# pi.net
KiCad netlist of a schematic drawn in EAGLE
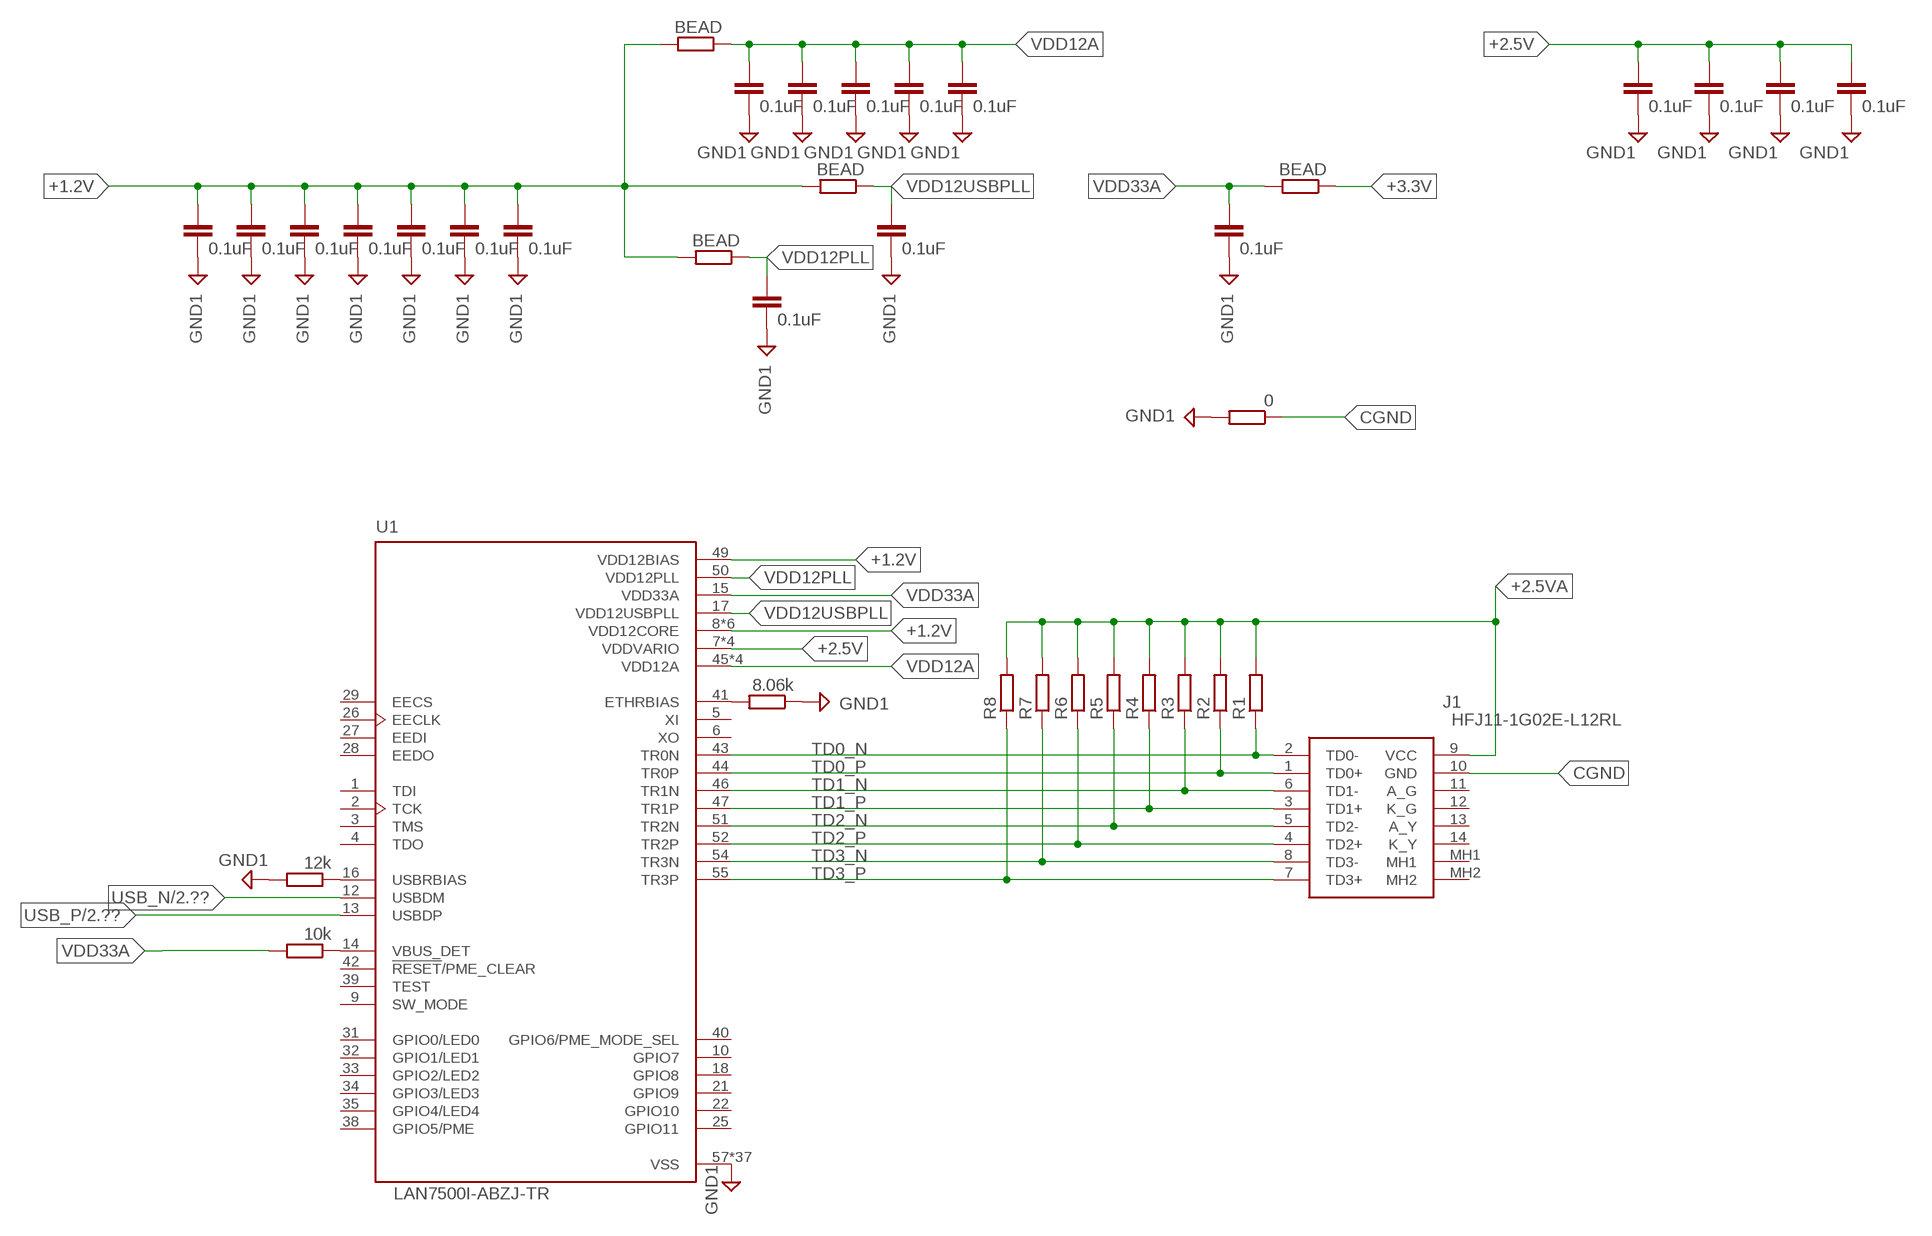
[diagram p0: schematic, sheet 1]
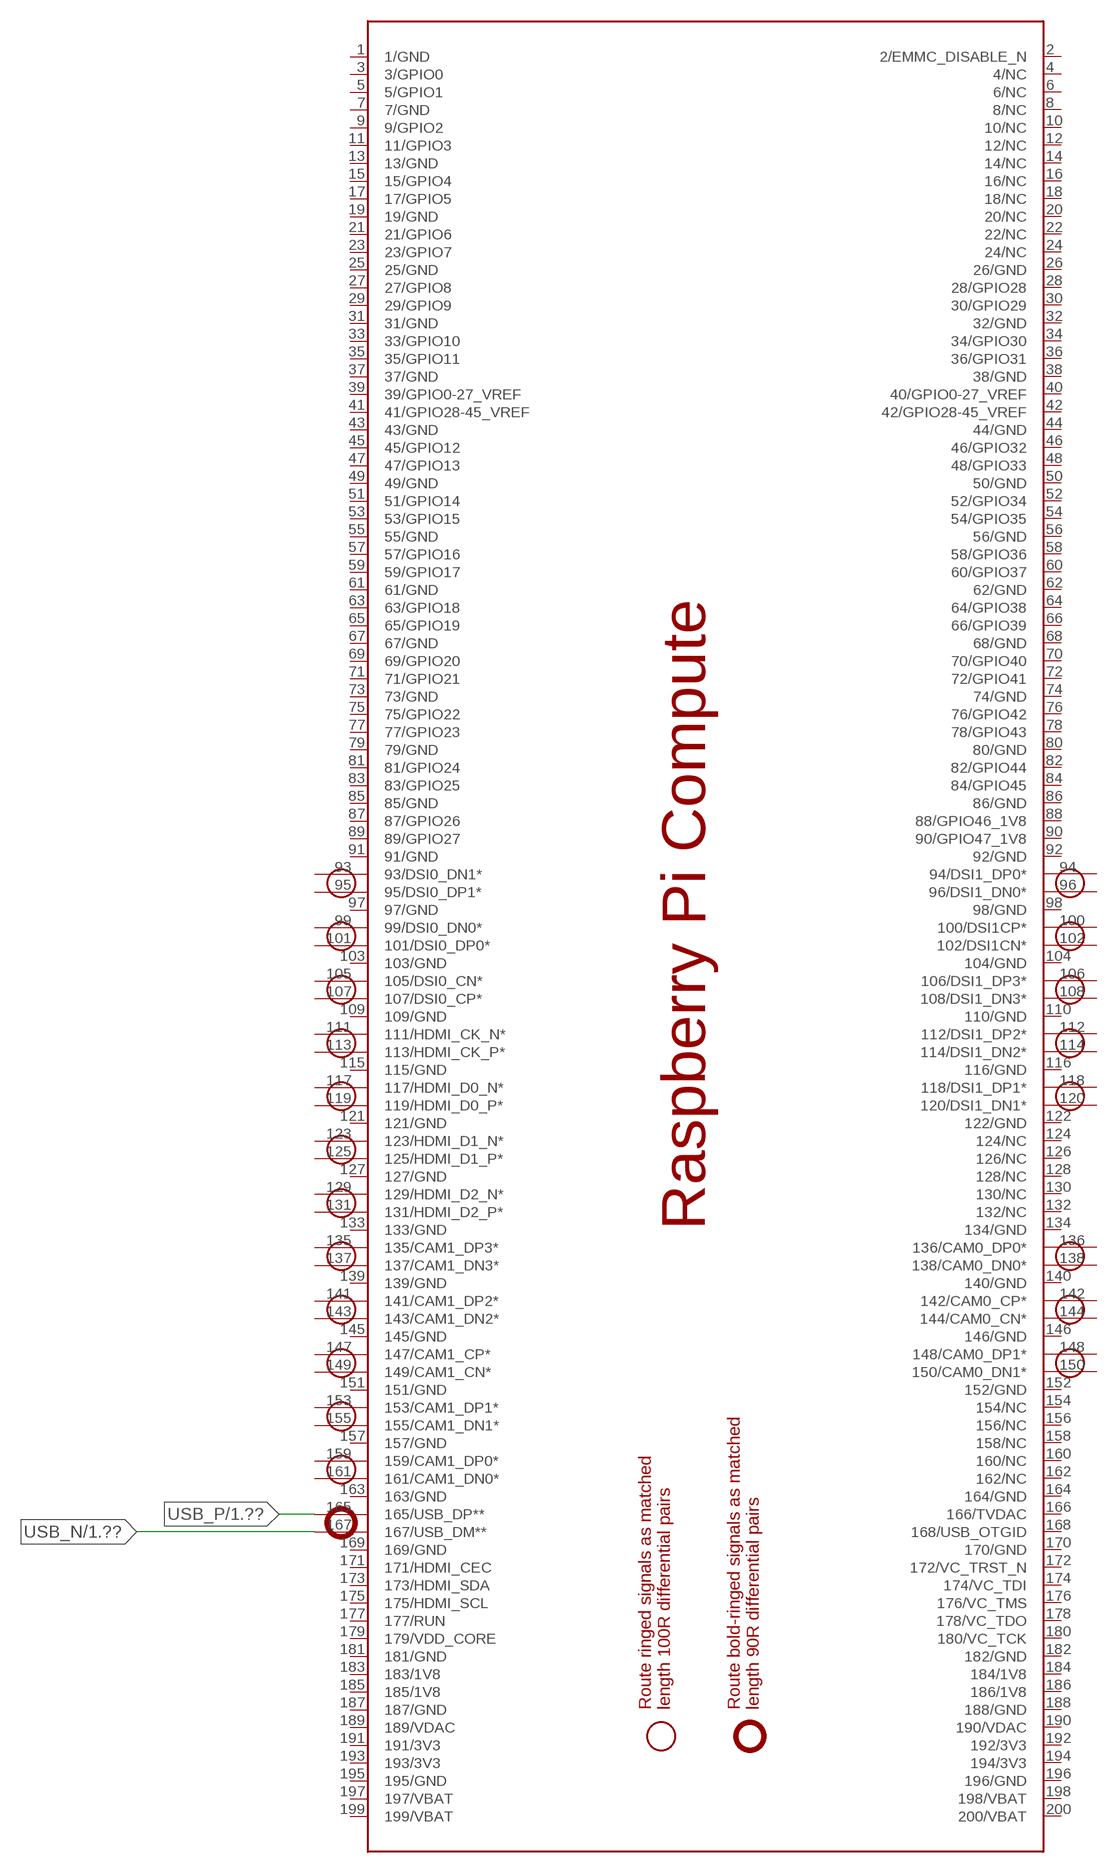
[diagram p1: schematic, sheet 2]
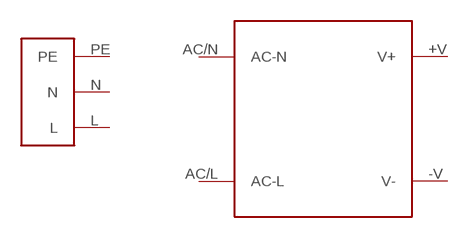
[diagram p2: schematic, sheet 3]

(export (version "E")
  (design (tool "Eeschema 10.0.6"))
  (components
    (comp (ref "U$1")
      (value "DD21")
      (footprint "eagle-import:DD21.NOCOVER")
      (libsource (lib "eagle-import") (part "DD21"))
    )
    (comp (ref "U$2")
      (value "IRM-15-5")
      (footprint "eagle-import:IRM-15")
      (libsource (lib "eagle-import") (part "IRM-15-5"))
    )
    (comp (ref "PCB1")
      (value "RPI_COMPUTE")
      (footprint "eagle-import:RPI_COMPUTE")
      (libsource (lib "eagle-import") (part "RPI_COMPUTE"))
    )
    (comp (ref "C1")
      (value "0.1uF")
      (footprint "eagle-import:C0603K")
      (libsource (lib "eagle-import") (part "C-EUC0603K"))
    )
    (comp (ref "C2")
      (value "0.1uF")
      (footprint "eagle-import:C0603K")
      (libsource (lib "eagle-import") (part "C-EUC0603K"))
    )
    (comp (ref "C3")
      (value "0.1uF")
      (footprint "eagle-import:C0603K")
      (libsource (lib "eagle-import") (part "C-EUC0603K"))
    )
    (comp (ref "C4")
      (value "0.1uF")
      (footprint "eagle-import:C0603K")
      (libsource (lib "eagle-import") (part "C-EUC0603K"))
    )
    (comp (ref "C5")
      (value "0.1uF")
      (footprint "eagle-import:C0603K")
      (libsource (lib "eagle-import") (part "C-EUC0603K"))
    )
    (comp (ref "C6")
      (value "0.1uF")
      (footprint "eagle-import:C0603K")
      (libsource (lib "eagle-import") (part "C-EUC0603K"))
    )
    (comp (ref "C7")
      (value "0.1uF")
      (footprint "eagle-import:C0603K")
      (libsource (lib "eagle-import") (part "C-EUC0603K"))
    )
    (comp (ref "C8")
      (value "0.1uF")
      (footprint "eagle-import:C0603K")
      (libsource (lib "eagle-import") (part "C-EUC0603K"))
    )
    (comp (ref "C9")
      (value "0.1uF")
      (footprint "eagle-import:C0603K")
      (libsource (lib "eagle-import") (part "C-EUC0603K"))
    )
    (comp (ref "C10")
      (value "0.1uF")
      (footprint "eagle-import:C0603K")
      (libsource (lib "eagle-import") (part "C-EUC0603K"))
    )
    (comp (ref "C11")
      (value "0.1uF")
      (footprint "eagle-import:C0603K")
      (libsource (lib "eagle-import") (part "C-EUC0603K"))
    )
    (comp (ref "C12")
      (value "0.1uF")
      (footprint "eagle-import:C0603K")
      (libsource (lib "eagle-import") (part "C-EUC0603K"))
    )
    (comp (ref "C13")
      (value "0.1uF")
      (footprint "eagle-import:C0603K")
      (libsource (lib "eagle-import") (part "C-EUC0603K"))
    )
    (comp (ref "C14")
      (value "0.1uF")
      (footprint "eagle-import:C0603K")
      (libsource (lib "eagle-import") (part "C-EUC0603K"))
    )
    (comp (ref "C15")
      (value "0.1uF")
      (footprint "eagle-import:C0603K")
      (libsource (lib "eagle-import") (part "C-EUC0603K"))
    )
    (comp (ref "C16")
      (value "0.1uF")
      (footprint "eagle-import:C0603K")
      (libsource (lib "eagle-import") (part "C-EUC0603K"))
    )
    (comp (ref "C17")
      (value "0.1uF")
      (footprint "eagle-import:C0603K")
      (libsource (lib "eagle-import") (part "C-EUC0603K"))
    )
    (comp (ref "C18")
      (value "0.1uF")
      (footprint "eagle-import:C0603K")
      (libsource (lib "eagle-import") (part "C-EUC0603K"))
    )
    (comp (ref "C19")
      (value "0.1uF")
      (footprint "eagle-import:C0603K")
      (libsource (lib "eagle-import") (part "C-EUC0603K"))
    )
    (comp (ref "J1")
      (value "HFJ11-1G02E-L12RL")
      (footprint "eagle-import:HFJ111G02EL12RL")
      (fields (field (name "MOUSER_PART_NUMBER") "493-HFJ111G02EL12RL"))
      (libsource (lib "eagle-import") (part "HFJ11-1G02E-L12RL"))
    )
    (comp (ref "R1")
      (value "R-EU_MELF0204R")
      (footprint "eagle-import:MINI_MELF-0204R")
      (libsource (lib "eagle-import") (part "R-EU_MELF0204R"))
    )
    (comp (ref "R2")
      (value "R-EU_MELF0204R")
      (footprint "eagle-import:MINI_MELF-0204R")
      (libsource (lib "eagle-import") (part "R-EU_MELF0204R"))
    )
    (comp (ref "R3")
      (value "R-EU_MELF0204R")
      (footprint "eagle-import:MINI_MELF-0204R")
      (libsource (lib "eagle-import") (part "R-EU_MELF0204R"))
    )
    (comp (ref "R4")
      (value "R-EU_MELF0204R")
      (footprint "eagle-import:MINI_MELF-0204R")
      (libsource (lib "eagle-import") (part "R-EU_MELF0204R"))
    )
    (comp (ref "R5")
      (value "R-EU_MELF0204R")
      (footprint "eagle-import:MINI_MELF-0204R")
      (libsource (lib "eagle-import") (part "R-EU_MELF0204R"))
    )
    (comp (ref "R6")
      (value "R-EU_MELF0204R")
      (footprint "eagle-import:MINI_MELF-0204R")
      (libsource (lib "eagle-import") (part "R-EU_MELF0204R"))
    )
    (comp (ref "R7")
      (value "R-EU_MELF0204R")
      (footprint "eagle-import:MINI_MELF-0204R")
      (libsource (lib "eagle-import") (part "R-EU_MELF0204R"))
    )
    (comp (ref "R8")
      (value "R-EU_MELF0204R")
      (footprint "eagle-import:MINI_MELF-0204R")
      (libsource (lib "eagle-import") (part "R-EU_MELF0204R"))
    )
    (comp (ref "R9")
      (value "8.06k")
      (footprint "eagle-import:MINI_MELF-0204R")
      (libsource (lib "eagle-import") (part "R-EU_MELF0204R"))
    )
    (comp (ref "R10")
      (value "12k")
      (footprint "eagle-import:MINI_MELF-0204R")
      (libsource (lib "eagle-import") (part "R-EU_MELF0204R"))
    )
    (comp (ref "R11")
      (value "10k")
      (footprint "eagle-import:MINI_MELF-0204R")
      (libsource (lib "eagle-import") (part "R-EU_MELF0204R"))
    )
    (comp (ref "R12")
      (value "BEAD")
      (footprint "eagle-import:MINI_MELF-0204R")
      (libsource (lib "eagle-import") (part "R-EU_MELF0204R"))
    )
    (comp (ref "R13")
      (value "BEAD")
      (footprint "eagle-import:MINI_MELF-0204R")
      (libsource (lib "eagle-import") (part "R-EU_MELF0204R"))
    )
    (comp (ref "R14")
      (value "BEAD")
      (footprint "eagle-import:MINI_MELF-0204R")
      (libsource (lib "eagle-import") (part "R-EU_MELF0204R"))
    )
    (comp (ref "R15")
      (value "0")
      (footprint "eagle-import:MINI_MELF-0204R")
      (libsource (lib "eagle-import") (part "R-EU_MELF0204R"))
    )
    (comp (ref "R16")
      (value "BEAD")
      (footprint "eagle-import:MINI_MELF-0204R")
      (libsource (lib "eagle-import") (part "R-EU_MELF0204R"))
    )
    (comp (ref "U1")
      (value "LAN7500I-ABZJ-TR")
      (footprint "eagle-import:QFN50P800X800X100-57N")
      (fields (field (name "MF") "Microchip"))
      (libsource (lib "eagle-import") (part "LAN7500I-ABZJ-TR"))
    )
  )
  (nets
    (net (code "1") (name "+1.2V") (class "Default")
      (node (ref "C19") (pin "1") (pinfunction "1_1") (pintype "passive"))
      (node (ref "C4") (pin "1") (pinfunction "1_1") (pintype "passive"))
      (node (ref "C5") (pin "1") (pinfunction "1_1") (pintype "passive"))
      (node (ref "C6") (pin "1") (pinfunction "1_1") (pintype "passive"))
      (node (ref "C7") (pin "1") (pinfunction "1_1") (pintype "passive"))
      (node (ref "C8") (pin "1") (pinfunction "1_1") (pintype "passive"))
      (node (ref "C9") (pin "1") (pinfunction "1_1") (pintype "passive"))
      (node (ref "R12") (pin "2") (pinfunction "2_2") (pintype "passive"))
      (node (ref "R13") (pin "2") (pinfunction "2_2") (pintype "passive"))
      (node (ref "R16") (pin "2") (pinfunction "2_2") (pintype "passive"))
      (node (ref "U1") (pin "11") (pinfunction "VDD12CORE_11") (pintype "power_in"))
      (node (ref "U1") (pin "20") (pinfunction "VDD12CORE_20") (pintype "power_in"))
      (node (ref "U1") (pin "23") (pinfunction "VDD12CORE_23") (pintype "power_in"))
      (node (ref "U1") (pin "30") (pinfunction "VDD12CORE_30") (pintype "power_in"))
      (node (ref "U1") (pin "36") (pinfunction "VDD12CORE_36") (pintype "power_in"))
      (node (ref "U1") (pin "49") (pinfunction "VDD12BIAS_49") (pintype "power_in"))
      (node (ref "U1") (pin "8") (pinfunction "VDD12CORE_8") (pintype "power_in"))
    )
    (net (code "2") (name "+2.5V") (class "Default")
      (node (ref "C15") (pin "1") (pinfunction "1_1") (pintype "passive"))
      (node (ref "C16") (pin "1") (pinfunction "1_1") (pintype "passive"))
      (node (ref "C17") (pin "1") (pinfunction "1_1") (pintype "passive"))
      (node (ref "C18") (pin "1") (pinfunction "1_1") (pintype "passive"))
      (node (ref "U1") (pin "19") (pinfunction "VDDVARIO_19") (pintype "power_in"))
      (node (ref "U1") (pin "24") (pinfunction "VDDVARIO_24") (pintype "power_in"))
      (node (ref "U1") (pin "37") (pinfunction "VDDVARIO_37") (pintype "power_in"))
      (node (ref "U1") (pin "7") (pinfunction "VDDVARIO_7") (pintype "power_in"))
    )
    (net (code "3") (name "+2.5VA") (class "Default")
      (node (ref "J1") (pin "9") (pinfunction "VCC_9") (pintype "bidirectional"))
      (node (ref "R1") (pin "2") (pinfunction "2_2") (pintype "passive"))
      (node (ref "R2") (pin "2") (pinfunction "2_2") (pintype "passive"))
      (node (ref "R3") (pin "2") (pinfunction "2_2") (pintype "passive"))
      (node (ref "R4") (pin "2") (pinfunction "2_2") (pintype "passive"))
      (node (ref "R5") (pin "2") (pinfunction "2_2") (pintype "passive"))
      (node (ref "R6") (pin "2") (pinfunction "2_2") (pintype "passive"))
      (node (ref "R7") (pin "2") (pinfunction "2_2") (pintype "passive"))
      (node (ref "R8") (pin "2") (pinfunction "2_2") (pintype "passive"))
    )
    (net (code "4") (name "+3.3V") (class "Default")
      (node (ref "R14") (pin "1") (pinfunction "1_1") (pintype "passive"))
    )
    (net (code "5") (name "CGND") (class "Default")
      (node (ref "J1") (pin "10") (pinfunction "GND_10") (pintype "bidirectional"))
      (node (ref "R15") (pin "1") (pinfunction "1_1") (pintype "passive"))
    )
    (net (code "6") (name "GND1") (class "Default")
      (node (ref "C1") (pin "2") (pinfunction "2_2") (pintype "passive"))
      (node (ref "C10") (pin "2") (pinfunction "2_2") (pintype "passive"))
      (node (ref "C11") (pin "2") (pinfunction "2_2") (pintype "passive"))
      (node (ref "C12") (pin "2") (pinfunction "2_2") (pintype "passive"))
      (node (ref "C13") (pin "2") (pinfunction "2_2") (pintype "passive"))
      (node (ref "C14") (pin "2") (pinfunction "2_2") (pintype "passive"))
      (node (ref "C15") (pin "2") (pinfunction "2_2") (pintype "passive"))
      (node (ref "C16") (pin "2") (pinfunction "2_2") (pintype "passive"))
      (node (ref "C17") (pin "2") (pinfunction "2_2") (pintype "passive"))
      (node (ref "C18") (pin "2") (pinfunction "2_2") (pintype "passive"))
      (node (ref "C19") (pin "2") (pinfunction "2_2") (pintype "passive"))
      (node (ref "C2") (pin "2") (pinfunction "2_2") (pintype "passive"))
      (node (ref "C3") (pin "2") (pinfunction "2_2") (pintype "passive"))
      (node (ref "C4") (pin "2") (pinfunction "2_2") (pintype "passive"))
      (node (ref "C5") (pin "2") (pinfunction "2_2") (pintype "passive"))
      (node (ref "C6") (pin "2") (pinfunction "2_2") (pintype "passive"))
      (node (ref "C7") (pin "2") (pinfunction "2_2") (pintype "passive"))
      (node (ref "C8") (pin "2") (pinfunction "2_2") (pintype "passive"))
      (node (ref "C9") (pin "2") (pinfunction "2_2") (pintype "passive"))
      (node (ref "R10") (pin "2") (pinfunction "2_2") (pintype "passive"))
      (node (ref "R15") (pin "2") (pinfunction "2_2") (pintype "passive"))
      (node (ref "R9") (pin "1") (pinfunction "1_1") (pintype "passive"))
      (node (ref "U1") (pin "57") (pinfunction "VSS_57") (pintype "power_in"))
      (node (ref "U1") (pin "V1") (pinfunction "VSS_V1") (pintype "power_in"))
      (node (ref "U1") (pin "V10") (pinfunction "VSS_V10") (pintype "power_in"))
      (node (ref "U1") (pin "V11") (pinfunction "VSS_V11") (pintype "power_in"))
      (node (ref "U1") (pin "V12") (pinfunction "VSS_V12") (pintype "power_in"))
      (node (ref "U1") (pin "V13") (pinfunction "VSS_V13") (pintype "power_in"))
      (node (ref "U1") (pin "V14") (pinfunction "VSS_V14") (pintype "power_in"))
      (node (ref "U1") (pin "V15") (pinfunction "VSS_V15") (pintype "power_in"))
      (node (ref "U1") (pin "V16") (pinfunction "VSS_V16") (pintype "power_in"))
      (node (ref "U1") (pin "V17") (pinfunction "VSS_V17") (pintype "power_in"))
      (node (ref "U1") (pin "V18") (pinfunction "VSS_V18") (pintype "power_in"))
      (node (ref "U1") (pin "V19") (pinfunction "VSS_V19") (pintype "power_in"))
      (node (ref "U1") (pin "V2") (pinfunction "VSS_V2") (pintype "power_in"))
      (node (ref "U1") (pin "V20") (pinfunction "VSS_V20") (pintype "power_in"))
      (node (ref "U1") (pin "V21") (pinfunction "VSS_V21") (pintype "power_in"))
      (node (ref "U1") (pin "V22") (pinfunction "VSS_V22") (pintype "power_in"))
      (node (ref "U1") (pin "V23") (pinfunction "VSS_V23") (pintype "power_in"))
      (node (ref "U1") (pin "V24") (pinfunction "VSS_V24") (pintype "power_in"))
      (node (ref "U1") (pin "V25") (pinfunction "VSS_V25") (pintype "power_in"))
      (node (ref "U1") (pin "V26") (pinfunction "VSS_V26") (pintype "power_in"))
      (node (ref "U1") (pin "V27") (pinfunction "VSS_V27") (pintype "power_in"))
      (node (ref "U1") (pin "V28") (pinfunction "VSS_V28") (pintype "power_in"))
      (node (ref "U1") (pin "V29") (pinfunction "VSS_V29") (pintype "power_in"))
      (node (ref "U1") (pin "V3") (pinfunction "VSS_V3") (pintype "power_in"))
      (node (ref "U1") (pin "V30") (pinfunction "VSS_V30") (pintype "power_in"))
      (node (ref "U1") (pin "V31") (pinfunction "VSS_V31") (pintype "power_in"))
      (node (ref "U1") (pin "V32") (pinfunction "VSS_V32") (pintype "power_in"))
      (node (ref "U1") (pin "V33") (pinfunction "VSS_V33") (pintype "power_in"))
      (node (ref "U1") (pin "V34") (pinfunction "VSS_V34") (pintype "power_in"))
      (node (ref "U1") (pin "V35") (pinfunction "VSS_V35") (pintype "power_in"))
      (node (ref "U1") (pin "V36") (pinfunction "VSS_V36") (pintype "power_in"))
      (node (ref "U1") (pin "V4") (pinfunction "VSS_V4") (pintype "power_in"))
      (node (ref "U1") (pin "V5") (pinfunction "VSS_V5") (pintype "power_in"))
      (node (ref "U1") (pin "V6") (pinfunction "VSS_V6") (pintype "power_in"))
      (node (ref "U1") (pin "V7") (pinfunction "VSS_V7") (pintype "power_in"))
      (node (ref "U1") (pin "V8") (pinfunction "VSS_V8") (pintype "power_in"))
      (node (ref "U1") (pin "V9") (pinfunction "VSS_V9") (pintype "power_in"))
    )
    (net (code "7") (name "Net-(U1-ETHRBIAS)") (class "Default")
      (node (ref "R9") (pin "2") (pinfunction "2_2") (pintype "passive"))
      (node (ref "U1") (pin "41") (pinfunction "ETHRBIAS_41") (pintype "input"))
    )
    (net (code "8") (name "Net-(U1-USBRBIAS)") (class "Default")
      (node (ref "R10") (pin "1") (pinfunction "1_1") (pintype "passive"))
      (node (ref "U1") (pin "16") (pinfunction "USBRBIAS_16") (pintype "input"))
    )
    (net (code "9") (name "Net-(U1-VBUS_DET)") (class "Default")
      (node (ref "R11") (pin "1") (pinfunction "1_1") (pintype "passive"))
      (node (ref "U1") (pin "14") (pinfunction "VBUS_DET_14") (pintype "input"))
    )
    (net (code "10") (name "TD0_N") (class "Default")
      (node (ref "J1") (pin "2") (pinfunction "TD0-_2") (pintype "bidirectional"))
      (node (ref "R1") (pin "1") (pinfunction "1_1") (pintype "passive"))
      (node (ref "U1") (pin "43") (pinfunction "TR0N_43") (pintype "bidirectional"))
    )
    (net (code "11") (name "TD0_P") (class "Default")
      (node (ref "J1") (pin "1") (pinfunction "TD0+_1") (pintype "bidirectional"))
      (node (ref "R2") (pin "1") (pinfunction "1_1") (pintype "passive"))
      (node (ref "U1") (pin "44") (pinfunction "TR0P_44") (pintype "bidirectional"))
    )
    (net (code "12") (name "TD1_N") (class "Default")
      (node (ref "J1") (pin "6") (pinfunction "TD1-_6") (pintype "bidirectional"))
      (node (ref "R3") (pin "1") (pinfunction "1_1") (pintype "passive"))
      (node (ref "U1") (pin "46") (pinfunction "TR1N_46") (pintype "bidirectional"))
    )
    (net (code "13") (name "TD1_P") (class "Default")
      (node (ref "J1") (pin "3") (pinfunction "TD1+_3") (pintype "bidirectional"))
      (node (ref "R4") (pin "1") (pinfunction "1_1") (pintype "passive"))
      (node (ref "U1") (pin "47") (pinfunction "TR1P_47") (pintype "bidirectional"))
    )
    (net (code "14") (name "TD2_N") (class "Default")
      (node (ref "J1") (pin "5") (pinfunction "TD2-_5") (pintype "bidirectional"))
      (node (ref "R5") (pin "1") (pinfunction "1_1") (pintype "passive"))
      (node (ref "U1") (pin "51") (pinfunction "TR2N_51") (pintype "bidirectional"))
    )
    (net (code "15") (name "TD2_P") (class "Default")
      (node (ref "J1") (pin "4") (pinfunction "TD2+_4") (pintype "bidirectional"))
      (node (ref "R6") (pin "1") (pinfunction "1_1") (pintype "passive"))
      (node (ref "U1") (pin "52") (pinfunction "TR2P_52") (pintype "bidirectional"))
    )
    (net (code "16") (name "TD3_N") (class "Default")
      (node (ref "J1") (pin "8") (pinfunction "TD3-_8") (pintype "bidirectional"))
      (node (ref "R7") (pin "1") (pinfunction "1_1") (pintype "passive"))
      (node (ref "U1") (pin "54") (pinfunction "TR3N_54") (pintype "bidirectional"))
    )
    (net (code "17") (name "TD3_P") (class "Default")
      (node (ref "J1") (pin "7") (pinfunction "TD3+_7") (pintype "bidirectional"))
      (node (ref "R8") (pin "1") (pinfunction "1_1") (pintype "passive"))
      (node (ref "U1") (pin "55") (pinfunction "TR3P_55") (pintype "bidirectional"))
    )
    (net (code "18") (name "USB_N") (class "Default")
      (node (ref "PCB1") (pin "167") (pinfunction "167/USB_DM**_167") (pintype "bidirectional"))
      (node (ref "U1") (pin "12") (pinfunction "USBDM_12") (pintype "bidirectional"))
    )
    (net (code "19") (name "USB_P") (class "Default")
      (node (ref "PCB1") (pin "165") (pinfunction "165/USB_DP**_165") (pintype "bidirectional"))
      (node (ref "U1") (pin "13") (pinfunction "USBDP_13") (pintype "bidirectional"))
    )
    (net (code "20") (name "VDD12A") (class "Default")
      (node (ref "C10") (pin "1") (pinfunction "1_1") (pintype "passive"))
      (node (ref "C11") (pin "1") (pinfunction "1_1") (pintype "passive"))
      (node (ref "C12") (pin "1") (pinfunction "1_1") (pintype "passive"))
      (node (ref "C13") (pin "1") (pinfunction "1_1") (pintype "passive"))
      (node (ref "C14") (pin "1") (pinfunction "1_1") (pintype "passive"))
      (node (ref "R16") (pin "1") (pinfunction "1_1") (pintype "passive"))
      (node (ref "U1") (pin "45") (pinfunction "VDD12A_45") (pintype "power_in"))
      (node (ref "U1") (pin "48") (pinfunction "VDD12A_48") (pintype "power_in"))
      (node (ref "U1") (pin "53") (pinfunction "VDD12A_53") (pintype "power_in"))
      (node (ref "U1") (pin "56") (pinfunction "VDD12A_56") (pintype "power_in"))
    )
    (net (code "21") (name "VDD12PLL") (class "Default")
      (node (ref "C2") (pin "1") (pinfunction "1_1") (pintype "passive"))
      (node (ref "R13") (pin "1") (pinfunction "1_1") (pintype "passive"))
      (node (ref "U1") (pin "50") (pinfunction "VDD12PLL_50") (pintype "power_in"))
    )
    (net (code "22") (name "VDD12USBPLL") (class "Default")
      (node (ref "C1") (pin "1") (pinfunction "1_1") (pintype "passive"))
      (node (ref "R12") (pin "1") (pinfunction "1_1") (pintype "passive"))
      (node (ref "U1") (pin "17") (pinfunction "VDD12USBPLL_17") (pintype "power_in"))
    )
    (net (code "23") (name "VDD33A") (class "Default")
      (node (ref "C3") (pin "1") (pinfunction "1_1") (pintype "passive"))
      (node (ref "R11") (pin "2") (pinfunction "2_2") (pintype "passive"))
      (node (ref "R14") (pin "2") (pinfunction "2_2") (pintype "passive"))
      (node (ref "U1") (pin "15") (pinfunction "VDD33A_15") (pintype "power_in"))
    )
    (net (code "24") (name "unconnected-(J1-A_G-Pad11)") (class "Default")
      (node (ref "J1") (pin "11") (pinfunction "A_G_11") (pintype "bidirectional"))
    )
    (net (code "25") (name "unconnected-(J1-A_Y-Pad13)") (class "Default")
      (node (ref "J1") (pin "13") (pinfunction "A_Y_13") (pintype "bidirectional"))
    )
    (net (code "26") (name "unconnected-(J1-K_G-Pad12)") (class "Default")
      (node (ref "J1") (pin "12") (pinfunction "K_G_12") (pintype "bidirectional"))
    )
    (net (code "27") (name "unconnected-(J1-K_Y-Pad14)") (class "Default")
      (node (ref "J1") (pin "14") (pinfunction "K_Y_14") (pintype "bidirectional"))
    )
    (net (code "28") (name "unconnected-(J1-PadMH1)") (class "Default")
      (node (ref "J1") (pin "MH1") (pinfunction "MH1_MH1") (pintype "bidirectional"))
    )
    (net (code "29") (name "unconnected-(J1-PadMH2)") (class "Default")
      (node (ref "J1") (pin "MH2") (pinfunction "MH2_MH2") (pintype "bidirectional"))
    )
    (net (code "30") (name "unconnected-(PCB1-1{slash}GND-Pad1)") (class "Default")
      (node (ref "PCB1") (pin "1") (pinfunction "1/GND_1") (pintype "bidirectional"))
    )
    (net (code "31") (name "unconnected-(PCB1-2{slash}EMMC_DISABLE_N-Pad2)") (class "Default")
      (node (ref "PCB1") (pin "2") (pinfunction "2/EMMC_DISABLE_N_2") (pintype "bidirectional"))
    )
    (net (code "32") (name "unconnected-(PCB1-3{slash}GPIO0-Pad3)") (class "Default")
      (node (ref "PCB1") (pin "3") (pinfunction "3/GPIO0_3") (pintype "bidirectional"))
    )
    (net (code "33") (name "unconnected-(PCB1-4{slash}NC-Pad4)") (class "Default")
      (node (ref "PCB1") (pin "4") (pinfunction "4/NC_4") (pintype "bidirectional"))
    )
    (net (code "34") (name "unconnected-(PCB1-5{slash}GPIO1-Pad5)") (class "Default")
      (node (ref "PCB1") (pin "5") (pinfunction "5/GPIO1_5") (pintype "bidirectional"))
    )
    (net (code "35") (name "unconnected-(PCB1-6{slash}NC-Pad6)") (class "Default")
      (node (ref "PCB1") (pin "6") (pinfunction "6/NC_6") (pintype "bidirectional"))
    )
    (net (code "36") (name "unconnected-(PCB1-7{slash}GND-Pad7)") (class "Default")
      (node (ref "PCB1") (pin "7") (pinfunction "7/GND_7") (pintype "bidirectional"))
    )
    (net (code "37") (name "unconnected-(PCB1-8{slash}NC-Pad8)") (class "Default")
      (node (ref "PCB1") (pin "8") (pinfunction "8/NC_8") (pintype "bidirectional"))
    )
    (net (code "38") (name "unconnected-(PCB1-9{slash}GPIO2-Pad9)") (class "Default")
      (node (ref "PCB1") (pin "9") (pinfunction "9/GPIO2_9") (pintype "bidirectional"))
    )
    (net (code "39") (name "unconnected-(PCB1-10{slash}NC-Pad10)") (class "Default")
      (node (ref "PCB1") (pin "10") (pinfunction "10/NC_10") (pintype "bidirectional"))
    )
    (net (code "40") (name "unconnected-(PCB1-11{slash}GPIO3-Pad11)") (class "Default")
      (node (ref "PCB1") (pin "11") (pinfunction "11/GPIO3_11") (pintype "bidirectional"))
    )
    (net (code "41") (name "unconnected-(PCB1-12{slash}NC-Pad12)") (class "Default")
      (node (ref "PCB1") (pin "12") (pinfunction "12/NC_12") (pintype "bidirectional"))
    )
    (net (code "42") (name "unconnected-(PCB1-13{slash}GND-Pad13)") (class "Default")
      (node (ref "PCB1") (pin "13") (pinfunction "13/GND_13") (pintype "bidirectional"))
    )
    (net (code "43") (name "unconnected-(PCB1-14{slash}NC-Pad14)") (class "Default")
      (node (ref "PCB1") (pin "14") (pinfunction "14/NC_14") (pintype "bidirectional"))
    )
    (net (code "44") (name "unconnected-(PCB1-15{slash}GPIO4-Pad15)") (class "Default")
      (node (ref "PCB1") (pin "15") (pinfunction "15/GPIO4_15") (pintype "bidirectional"))
    )
    (net (code "45") (name "unconnected-(PCB1-16{slash}NC-Pad16)") (class "Default")
      (node (ref "PCB1") (pin "16") (pinfunction "16/NC_16") (pintype "bidirectional"))
    )
    (net (code "46") (name "unconnected-(PCB1-17{slash}GPIO5-Pad17)") (class "Default")
      (node (ref "PCB1") (pin "17") (pinfunction "17/GPIO5_17") (pintype "bidirectional"))
    )
    (net (code "47") (name "unconnected-(PCB1-18{slash}NC-Pad18)") (class "Default")
      (node (ref "PCB1") (pin "18") (pinfunction "18/NC_18") (pintype "bidirectional"))
    )
    (net (code "48") (name "unconnected-(PCB1-19{slash}GND-Pad19)") (class "Default")
      (node (ref "PCB1") (pin "19") (pinfunction "19/GND_19") (pintype "bidirectional"))
    )
    (net (code "49") (name "unconnected-(PCB1-20{slash}NC-Pad20)") (class "Default")
      (node (ref "PCB1") (pin "20") (pinfunction "20/NC_20") (pintype "bidirectional"))
    )
    (net (code "50") (name "unconnected-(PCB1-21{slash}GPIO6-Pad21)") (class "Default")
      (node (ref "PCB1") (pin "21") (pinfunction "21/GPIO6_21") (pintype "bidirectional"))
    )
    (net (code "51") (name "unconnected-(PCB1-22{slash}NC-Pad22)") (class "Default")
      (node (ref "PCB1") (pin "22") (pinfunction "22/NC_22") (pintype "bidirectional"))
    )
    (net (code "52") (name "unconnected-(PCB1-23{slash}GPIO7-Pad23)") (class "Default")
      (node (ref "PCB1") (pin "23") (pinfunction "23/GPIO7_23") (pintype "bidirectional"))
    )
    (net (code "53") (name "unconnected-(PCB1-24{slash}NC-Pad24)") (class "Default")
      (node (ref "PCB1") (pin "24") (pinfunction "24/NC_24") (pintype "bidirectional"))
    )
    (net (code "54") (name "unconnected-(PCB1-25{slash}GND-Pad25)") (class "Default")
      (node (ref "PCB1") (pin "25") (pinfunction "25/GND_25") (pintype "bidirectional"))
    )
    (net (code "55") (name "unconnected-(PCB1-26{slash}GND-Pad26)") (class "Default")
      (node (ref "PCB1") (pin "26") (pinfunction "26/GND_26") (pintype "bidirectional"))
    )
    (net (code "56") (name "unconnected-(PCB1-27{slash}GPIO8-Pad27)") (class "Default")
      (node (ref "PCB1") (pin "27") (pinfunction "27/GPIO8_27") (pintype "bidirectional"))
    )
    (net (code "57") (name "unconnected-(PCB1-28{slash}GPIO28-Pad28)") (class "Default")
      (node (ref "PCB1") (pin "28") (pinfunction "28/GPIO28_28") (pintype "bidirectional"))
    )
    (net (code "58") (name "unconnected-(PCB1-29{slash}GPIO9-Pad29)") (class "Default")
      (node (ref "PCB1") (pin "29") (pinfunction "29/GPIO9_29") (pintype "bidirectional"))
    )
    (net (code "59") (name "unconnected-(PCB1-30{slash}GPIO29-Pad30)") (class "Default")
      (node (ref "PCB1") (pin "30") (pinfunction "30/GPIO29_30") (pintype "bidirectional"))
    )
    (net (code "60") (name "unconnected-(PCB1-31{slash}GND-Pad31)") (class "Default")
      (node (ref "PCB1") (pin "31") (pinfunction "31/GND_31") (pintype "bidirectional"))
    )
    (net (code "61") (name "unconnected-(PCB1-32{slash}GND-Pad32)") (class "Default")
      (node (ref "PCB1") (pin "32") (pinfunction "32/GND_32") (pintype "bidirectional"))
    )
    (net (code "62") (name "unconnected-(PCB1-33{slash}GPIO10-Pad33)") (class "Default")
      (node (ref "PCB1") (pin "33") (pinfunction "33/GPIO10_33") (pintype "bidirectional"))
    )
    (net (code "63") (name "unconnected-(PCB1-34{slash}GPIO30-Pad34)") (class "Default")
      (node (ref "PCB1") (pin "34") (pinfunction "34/GPIO30_34") (pintype "bidirectional"))
    )
    (net (code "64") (name "unconnected-(PCB1-35{slash}GPIO11-Pad35)") (class "Default")
      (node (ref "PCB1") (pin "35") (pinfunction "35/GPIO11_35") (pintype "bidirectional"))
    )
    (net (code "65") (name "unconnected-(PCB1-36{slash}GPIO31-Pad36)") (class "Default")
      (node (ref "PCB1") (pin "36") (pinfunction "36/GPIO31_36") (pintype "bidirectional"))
    )
    (net (code "66") (name "unconnected-(PCB1-37{slash}GND-Pad37)") (class "Default")
      (node (ref "PCB1") (pin "37") (pinfunction "37/GND_37") (pintype "bidirectional"))
    )
    (net (code "67") (name "unconnected-(PCB1-38{slash}GND-Pad38)") (class "Default")
      (node (ref "PCB1") (pin "38") (pinfunction "38/GND_38") (pintype "bidirectional"))
    )
    (net (code "68") (name "unconnected-(PCB1-39{slash}GPIO0-27_VREF-Pad39)") (class "Default")
      (node (ref "PCB1") (pin "39") (pinfunction "39/GPIO0-27_VREF_39") (pintype "bidirectional"))
    )
    (net (code "69") (name "unconnected-(PCB1-40{slash}GPIO0-27_VREF-Pad40)") (class "Default")
      (node (ref "PCB1") (pin "40") (pinfunction "40/GPIO0-27_VREF_40") (pintype "bidirectional"))
    )
    (net (code "70") (name "unconnected-(PCB1-41{slash}GPIO28-45_VREF-Pad41)") (class "Default")
      (node (ref "PCB1") (pin "41") (pinfunction "41/GPIO28-45_VREF_41") (pintype "bidirectional"))
    )
    (net (code "71") (name "unconnected-(PCB1-42{slash}GPIO28-45_VREF-Pad42)") (class "Default")
      (node (ref "PCB1") (pin "42") (pinfunction "42/GPIO28-45_VREF_42") (pintype "bidirectional"))
    )
    (net (code "72") (name "unconnected-(PCB1-43{slash}GND-Pad43)") (class "Default")
      (node (ref "PCB1") (pin "43") (pinfunction "43/GND_43") (pintype "bidirectional"))
    )
    (net (code "73") (name "unconnected-(PCB1-44{slash}GND-Pad44)") (class "Default")
      (node (ref "PCB1") (pin "44") (pinfunction "44/GND_44") (pintype "bidirectional"))
    )
    (net (code "74") (name "unconnected-(PCB1-45{slash}GPIO12-Pad45)") (class "Default")
      (node (ref "PCB1") (pin "45") (pinfunction "45/GPIO12_45") (pintype "bidirectional"))
    )
    (net (code "75") (name "unconnected-(PCB1-46{slash}GPIO32-Pad46)") (class "Default")
      (node (ref "PCB1") (pin "46") (pinfunction "46/GPIO32_46") (pintype "bidirectional"))
    )
    (net (code "76") (name "unconnected-(PCB1-47{slash}GPIO13-Pad47)") (class "Default")
      (node (ref "PCB1") (pin "47") (pinfunction "47/GPIO13_47") (pintype "bidirectional"))
    )
    (net (code "77") (name "unconnected-(PCB1-48{slash}GPIO33-Pad48)") (class "Default")
      (node (ref "PCB1") (pin "48") (pinfunction "48/GPIO33_48") (pintype "bidirectional"))
    )
    (net (code "78") (name "unconnected-(PCB1-49{slash}GND-Pad49)") (class "Default")
      (node (ref "PCB1") (pin "49") (pinfunction "49/GND_49") (pintype "bidirectional"))
    )
    (net (code "79") (name "unconnected-(PCB1-50{slash}GND-Pad50)") (class "Default")
      (node (ref "PCB1") (pin "50") (pinfunction "50/GND_50") (pintype "bidirectional"))
    )
    (net (code "80") (name "unconnected-(PCB1-51{slash}GPIO14-Pad51)") (class "Default")
      (node (ref "PCB1") (pin "51") (pinfunction "51/GPIO14_51") (pintype "bidirectional"))
    )
    (net (code "81") (name "unconnected-(PCB1-52{slash}GPIO34-Pad52)") (class "Default")
      (node (ref "PCB1") (pin "52") (pinfunction "52/GPIO34_52") (pintype "bidirectional"))
    )
    (net (code "82") (name "unconnected-(PCB1-53{slash}GPIO15-Pad53)") (class "Default")
      (node (ref "PCB1") (pin "53") (pinfunction "53/GPIO15_53") (pintype "bidirectional"))
    )
    (net (code "83") (name "unconnected-(PCB1-54{slash}GPIO35-Pad54)") (class "Default")
      (node (ref "PCB1") (pin "54") (pinfunction "54/GPIO35_54") (pintype "bidirectional"))
    )
    (net (code "84") (name "unconnected-(PCB1-55{slash}GND-Pad55)") (class "Default")
      (node (ref "PCB1") (pin "55") (pinfunction "55/GND_55") (pintype "bidirectional"))
    )
    (net (code "85") (name "unconnected-(PCB1-56{slash}GND-Pad56)") (class "Default")
      (node (ref "PCB1") (pin "56") (pinfunction "56/GND_56") (pintype "bidirectional"))
    )
    (net (code "86") (name "unconnected-(PCB1-57{slash}GPIO16-Pad57)") (class "Default")
      (node (ref "PCB1") (pin "57") (pinfunction "57/GPIO16_57") (pintype "bidirectional"))
    )
    (net (code "87") (name "unconnected-(PCB1-58{slash}GPIO36-Pad58)") (class "Default")
      (node (ref "PCB1") (pin "58") (pinfunction "58/GPIO36_58") (pintype "bidirectional"))
    )
    (net (code "88") (name "unconnected-(PCB1-59{slash}GPIO17-Pad59)") (class "Default")
      (node (ref "PCB1") (pin "59") (pinfunction "59/GPIO17_59") (pintype "bidirectional"))
    )
    (net (code "89") (name "unconnected-(PCB1-60{slash}GPIO37-Pad60)") (class "Default")
      (node (ref "PCB1") (pin "60") (pinfunction "60/GPIO37_60") (pintype "bidirectional"))
    )
    (net (code "90") (name "unconnected-(PCB1-61{slash}GND-Pad61)") (class "Default")
      (node (ref "PCB1") (pin "61") (pinfunction "61/GND_61") (pintype "bidirectional"))
    )
    (net (code "91") (name "unconnected-(PCB1-62{slash}GND-Pad62)") (class "Default")
      (node (ref "PCB1") (pin "62") (pinfunction "62/GND_62") (pintype "bidirectional"))
    )
    (net (code "92") (name "unconnected-(PCB1-63{slash}GPIO18-Pad63)") (class "Default")
      (node (ref "PCB1") (pin "63") (pinfunction "63/GPIO18_63") (pintype "bidirectional"))
    )
    (net (code "93") (name "unconnected-(PCB1-64{slash}GPIO38-Pad64)") (class "Default")
      (node (ref "PCB1") (pin "64") (pinfunction "64/GPIO38_64") (pintype "bidirectional"))
    )
    (net (code "94") (name "unconnected-(PCB1-65{slash}GPIO19-Pad65)") (class "Default")
      (node (ref "PCB1") (pin "65") (pinfunction "65/GPIO19_65") (pintype "bidirectional"))
    )
    (net (code "95") (name "unconnected-(PCB1-66{slash}GPIO39-Pad66)") (class "Default")
      (node (ref "PCB1") (pin "66") (pinfunction "66/GPIO39_66") (pintype "bidirectional"))
    )
    (net (code "96") (name "unconnected-(PCB1-67{slash}GND-Pad67)") (class "Default")
      (node (ref "PCB1") (pin "67") (pinfunction "67/GND_67") (pintype "bidirectional"))
    )
    (net (code "97") (name "unconnected-(PCB1-68{slash}GND-Pad68)") (class "Default")
      (node (ref "PCB1") (pin "68") (pinfunction "68/GND_68") (pintype "bidirectional"))
    )
    (net (code "98") (name "unconnected-(PCB1-69{slash}GPIO20-Pad69)") (class "Default")
      (node (ref "PCB1") (pin "69") (pinfunction "69/GPIO20_69") (pintype "bidirectional"))
    )
    (net (code "99") (name "unconnected-(PCB1-70{slash}GPIO40-Pad70)") (class "Default")
      (node (ref "PCB1") (pin "70") (pinfunction "70/GPIO40_70") (pintype "bidirectional"))
    )
    (net (code "100") (name "unconnected-(PCB1-71{slash}GPIO21-Pad71)") (class "Default")
      (node (ref "PCB1") (pin "71") (pinfunction "71/GPIO21_71") (pintype "bidirectional"))
    )
    (net (code "101") (name "unconnected-(PCB1-72{slash}GPIO41-Pad72)") (class "Default")
      (node (ref "PCB1") (pin "72") (pinfunction "72/GPIO41_72") (pintype "bidirectional"))
    )
    (net (code "102") (name "unconnected-(PCB1-73{slash}GND-Pad73)") (class "Default")
      (node (ref "PCB1") (pin "73") (pinfunction "73/GND_73") (pintype "bidirectional"))
    )
    (net (code "103") (name "unconnected-(PCB1-74{slash}GND-Pad74)") (class "Default")
      (node (ref "PCB1") (pin "74") (pinfunction "74/GND_74") (pintype "bidirectional"))
    )
    (net (code "104") (name "unconnected-(PCB1-75{slash}GPIO22-Pad75)") (class "Default")
      (node (ref "PCB1") (pin "75") (pinfunction "75/GPIO22_75") (pintype "bidirectional"))
    )
    (net (code "105") (name "unconnected-(PCB1-76{slash}GPIO42-Pad76)") (class "Default")
      (node (ref "PCB1") (pin "76") (pinfunction "76/GPIO42_76") (pintype "bidirectional"))
    )
    (net (code "106") (name "unconnected-(PCB1-77{slash}GPIO23-Pad77)") (class "Default")
      (node (ref "PCB1") (pin "77") (pinfunction "77/GPIO23_77") (pintype "bidirectional"))
    )
    (net (code "107") (name "unconnected-(PCB1-78{slash}GPIO43-Pad78)") (class "Default")
      (node (ref "PCB1") (pin "78") (pinfunction "78/GPIO43_78") (pintype "bidirectional"))
    )
    (net (code "108") (name "unconnected-(PCB1-79{slash}GND-Pad79)") (class "Default")
      (node (ref "PCB1") (pin "79") (pinfunction "79/GND_79") (pintype "bidirectional"))
    )
    (net (code "109") (name "unconnected-(PCB1-80{slash}GND-Pad80)") (class "Default")
      (node (ref "PCB1") (pin "80") (pinfunction "80/GND_80") (pintype "bidirectional"))
    )
    (net (code "110") (name "unconnected-(PCB1-81{slash}GPIO24-Pad81)") (class "Default")
      (node (ref "PCB1") (pin "81") (pinfunction "81/GPIO24_81") (pintype "bidirectional"))
    )
    (net (code "111") (name "unconnected-(PCB1-82{slash}GPIO44-Pad82)") (class "Default")
      (node (ref "PCB1") (pin "82") (pinfunction "82/GPIO44_82") (pintype "bidirectional"))
    )
    (net (code "112") (name "unconnected-(PCB1-83{slash}GPIO25-Pad83)") (class "Default")
      (node (ref "PCB1") (pin "83") (pinfunction "83/GPIO25_83") (pintype "bidirectional"))
    )
    (net (code "113") (name "unconnected-(PCB1-84{slash}GPIO45-Pad84)") (class "Default")
      (node (ref "PCB1") (pin "84") (pinfunction "84/GPIO45_84") (pintype "bidirectional"))
    )
    (net (code "114") (name "unconnected-(PCB1-85{slash}GND-Pad85)") (class "Default")
      (node (ref "PCB1") (pin "85") (pinfunction "85/GND_85") (pintype "bidirectional"))
    )
    (net (code "115") (name "unconnected-(PCB1-86{slash}GND-Pad86)") (class "Default")
      (node (ref "PCB1") (pin "86") (pinfunction "86/GND_86") (pintype "bidirectional"))
    )
    (net (code "116") (name "unconnected-(PCB1-87{slash}GPIO26-Pad87)") (class "Default")
      (node (ref "PCB1") (pin "87") (pinfunction "87/GPIO26_87") (pintype "bidirectional"))
    )
    (net (code "117") (name "unconnected-(PCB1-88{slash}GPIO46_1V8-Pad88)") (class "Default")
      (node (ref "PCB1") (pin "88") (pinfunction "88/GPIO46_1V8_88") (pintype "bidirectional"))
    )
    (net (code "118") (name "unconnected-(PCB1-89{slash}GPIO27-Pad89)") (class "Default")
      (node (ref "PCB1") (pin "89") (pinfunction "89/GPIO27_89") (pintype "bidirectional"))
    )
    (net (code "119") (name "unconnected-(PCB1-90{slash}GPIO47_1V8-Pad90)") (class "Default")
      (node (ref "PCB1") (pin "90") (pinfunction "90/GPIO47_1V8_90") (pintype "bidirectional"))
    )
    (net (code "120") (name "unconnected-(PCB1-91{slash}GND-Pad91)") (class "Default")
      (node (ref "PCB1") (pin "91") (pinfunction "91/GND_91") (pintype "bidirectional"))
    )
    (net (code "121") (name "unconnected-(PCB1-92{slash}GND-Pad92)") (class "Default")
      (node (ref "PCB1") (pin "92") (pinfunction "92/GND_92") (pintype "bidirectional"))
    )
    (net (code "122") (name "unconnected-(PCB1-93{slash}DSI0_DN1*-Pad93)") (class "Default")
      (node (ref "PCB1") (pin "93") (pinfunction "93/DSI0_DN1*_93") (pintype "bidirectional"))
    )
    (net (code "123") (name "unconnected-(PCB1-94{slash}DSI1_DP0*-Pad94)") (class "Default")
      (node (ref "PCB1") (pin "94") (pinfunction "94/DSI1_DP0*_94") (pintype "bidirectional"))
    )
    (net (code "124") (name "unconnected-(PCB1-95{slash}DSI0_DP1*-Pad95)") (class "Default")
      (node (ref "PCB1") (pin "95") (pinfunction "95/DSI0_DP1*_95") (pintype "bidirectional"))
    )
    (net (code "125") (name "unconnected-(PCB1-96{slash}DSI1_DN0*-Pad96)") (class "Default")
      (node (ref "PCB1") (pin "96") (pinfunction "96/DSI1_DN0*_96") (pintype "bidirectional"))
    )
    (net (code "126") (name "unconnected-(PCB1-97{slash}GND-Pad97)") (class "Default")
      (node (ref "PCB1") (pin "97") (pinfunction "97/GND_97") (pintype "bidirectional"))
    )
    (net (code "127") (name "unconnected-(PCB1-98{slash}GND-Pad98)") (class "Default")
      (node (ref "PCB1") (pin "98") (pinfunction "98/GND_98") (pintype "bidirectional"))
    )
    (net (code "128") (name "unconnected-(PCB1-99{slash}DSI0_DN0*-Pad99)") (class "Default")
      (node (ref "PCB1") (pin "99") (pinfunction "99/DSI0_DN0*_99") (pintype "bidirectional"))
    )
    (net (code "129") (name "unconnected-(PCB1-100{slash}DSI1CP*-Pad100)") (class "Default")
      (node (ref "PCB1") (pin "100") (pinfunction "100/DSI1CP*_100") (pintype "bidirectional"))
    )
    (net (code "130") (name "unconnected-(PCB1-101{slash}DSI0_DP0*-Pad101)") (class "Default")
      (node (ref "PCB1") (pin "101") (pinfunction "101/DSI0_DP0*_101") (pintype "bidirectional"))
    )
    (net (code "131") (name "unconnected-(PCB1-102{slash}DSI1CN*-Pad102)") (class "Default")
      (node (ref "PCB1") (pin "102") (pinfunction "102/DSI1CN*_102") (pintype "bidirectional"))
    )
    (net (code "132") (name "unconnected-(PCB1-103{slash}GND-Pad103)") (class "Default")
      (node (ref "PCB1") (pin "103") (pinfunction "103/GND_103") (pintype "bidirectional"))
    )
    (net (code "133") (name "unconnected-(PCB1-104{slash}GND-Pad104)") (class "Default")
      (node (ref "PCB1") (pin "104") (pinfunction "104/GND_104") (pintype "bidirectional"))
    )
    (net (code "134") (name "unconnected-(PCB1-105{slash}DSI0_CN*-Pad105)") (class "Default")
      (node (ref "PCB1") (pin "105") (pinfunction "105/DSI0_CN*_105") (pintype "bidirectional"))
    )
    (net (code "135") (name "unconnected-(PCB1-106{slash}DSI1_DP3*-Pad106)") (class "Default")
      (node (ref "PCB1") (pin "106") (pinfunction "106/DSI1_DP3*_106") (pintype "bidirectional"))
    )
    (net (code "136") (name "unconnected-(PCB1-107{slash}DSI0_CP*-Pad107)") (class "Default")
      (node (ref "PCB1") (pin "107") (pinfunction "107/DSI0_CP*_107") (pintype "bidirectional"))
    )
    (net (code "137") (name "unconnected-(PCB1-108{slash}DSI1_DN3*-Pad108)") (class "Default")
      (node (ref "PCB1") (pin "108") (pinfunction "108/DSI1_DN3*_108") (pintype "bidirectional"))
    )
    (net (code "138") (name "unconnected-(PCB1-109{slash}GND-Pad109)") (class "Default")
      (node (ref "PCB1") (pin "109") (pinfunction "109/GND_109") (pintype "bidirectional"))
    )
    (net (code "139") (name "unconnected-(PCB1-110{slash}GND-Pad110)") (class "Default")
      (node (ref "PCB1") (pin "110") (pinfunction "110/GND_110") (pintype "bidirectional"))
    )
    (net (code "140") (name "unconnected-(PCB1-111{slash}HDMI_CK_N*-Pad111)") (class "Default")
      (node (ref "PCB1") (pin "111") (pinfunction "111/HDMI_CK_N*_111") (pintype "bidirectional"))
    )
    (net (code "141") (name "unconnected-(PCB1-112{slash}DSI1_DP2*-Pad112)") (class "Default")
      (node (ref "PCB1") (pin "112") (pinfunction "112/DSI1_DP2*_112") (pintype "bidirectional"))
    )
    (net (code "142") (name "unconnected-(PCB1-113{slash}HDMI_CK_P*-Pad113)") (class "Default")
      (node (ref "PCB1") (pin "113") (pinfunction "113/HDMI_CK_P*_113") (pintype "bidirectional"))
    )
    (net (code "143") (name "unconnected-(PCB1-114{slash}DSI1_DN2*-Pad114)") (class "Default")
      (node (ref "PCB1") (pin "114") (pinfunction "114/DSI1_DN2*_114") (pintype "bidirectional"))
    )
    (net (code "144") (name "unconnected-(PCB1-115{slash}GND-Pad115)") (class "Default")
      (node (ref "PCB1") (pin "115") (pinfunction "115/GND_115") (pintype "bidirectional"))
    )
    (net (code "145") (name "unconnected-(PCB1-116{slash}GND-Pad116)") (class "Default")
      (node (ref "PCB1") (pin "116") (pinfunction "116/GND_116") (pintype "bidirectional"))
    )
    (net (code "146") (name "unconnected-(PCB1-117{slash}HDMI_D0_N*-Pad117)") (class "Default")
      (node (ref "PCB1") (pin "117") (pinfunction "117/HDMI_D0_N*_117") (pintype "bidirectional"))
    )
    (net (code "147") (name "unconnected-(PCB1-118{slash}DSI1_DP1*-Pad118)") (class "Default")
      (node (ref "PCB1") (pin "118") (pinfunction "118/DSI1_DP1*_118") (pintype "bidirectional"))
    )
    (net (code "148") (name "unconnected-(PCB1-119{slash}HDMI_D0_P*-Pad119)") (class "Default")
      (node (ref "PCB1") (pin "119") (pinfunction "119/HDMI_D0_P*_119") (pintype "bidirectional"))
    )
    (net (code "149") (name "unconnected-(PCB1-120{slash}DSI1_DN1*-Pad120)") (class "Default")
      (node (ref "PCB1") (pin "120") (pinfunction "120/DSI1_DN1*_120") (pintype "bidirectional"))
    )
    (net (code "150") (name "unconnected-(PCB1-121{slash}GND-Pad121)") (class "Default")
      (node (ref "PCB1") (pin "121") (pinfunction "121/GND_121") (pintype "bidirectional"))
    )
    (net (code "151") (name "unconnected-(PCB1-122{slash}GND-Pad122)") (class "Default")
      (node (ref "PCB1") (pin "122") (pinfunction "122/GND_122") (pintype "bidirectional"))
    )
    (net (code "152") (name "unconnected-(PCB1-123{slash}HDMI_D1_N*-Pad123)") (class "Default")
      (node (ref "PCB1") (pin "123") (pinfunction "123/HDMI_D1_N*_123") (pintype "bidirectional"))
    )
    (net (code "153") (name "unconnected-(PCB1-124{slash}NC-Pad124)") (class "Default")
      (node (ref "PCB1") (pin "124") (pinfunction "124/NC_124") (pintype "bidirectional"))
    )
    (net (code "154") (name "unconnected-(PCB1-125{slash}HDMI_D1_P*-Pad125)") (class "Default")
      (node (ref "PCB1") (pin "125") (pinfunction "125/HDMI_D1_P*_125") (pintype "bidirectional"))
    )
    (net (code "155") (name "unconnected-(PCB1-126{slash}NC-Pad126)") (class "Default")
      (node (ref "PCB1") (pin "126") (pinfunction "126/NC_126") (pintype "bidirectional"))
    )
    (net (code "156") (name "unconnected-(PCB1-127{slash}GND-Pad127)") (class "Default")
      (node (ref "PCB1") (pin "127") (pinfunction "127/GND_127") (pintype "bidirectional"))
    )
    (net (code "157") (name "unconnected-(PCB1-128{slash}NC-Pad128)") (class "Default")
      (node (ref "PCB1") (pin "128") (pinfunction "128/NC_128") (pintype "bidirectional"))
    )
    (net (code "158") (name "unconnected-(PCB1-129{slash}HDMI_D2_N*-Pad129)") (class "Default")
      (node (ref "PCB1") (pin "129") (pinfunction "129/HDMI_D2_N*_129") (pintype "bidirectional"))
    )
    (net (code "159") (name "unconnected-(PCB1-130{slash}NC-Pad130)") (class "Default")
      (node (ref "PCB1") (pin "130") (pinfunction "130/NC_130") (pintype "bidirectional"))
    )
    (net (code "160") (name "unconnected-(PCB1-131{slash}HDMI_D2_P*-Pad131)") (class "Default")
      (node (ref "PCB1") (pin "131") (pinfunction "131/HDMI_D2_P*_131") (pintype "bidirectional"))
    )
    (net (code "161") (name "unconnected-(PCB1-132{slash}NC-Pad132)") (class "Default")
      (node (ref "PCB1") (pin "132") (pinfunction "132/NC_132") (pintype "bidirectional"))
    )
    (net (code "162") (name "unconnected-(PCB1-133{slash}GND-Pad133)") (class "Default")
      (node (ref "PCB1") (pin "133") (pinfunction "133/GND_133") (pintype "bidirectional"))
    )
    (net (code "163") (name "unconnected-(PCB1-134{slash}GND-Pad134)") (class "Default")
      (node (ref "PCB1") (pin "134") (pinfunction "134/GND_134") (pintype "bidirectional"))
    )
    (net (code "164") (name "unconnected-(PCB1-135{slash}CAM1_DP3*-Pad135)") (class "Default")
      (node (ref "PCB1") (pin "135") (pinfunction "135/CAM1_DP3*_135") (pintype "bidirectional"))
    )
    (net (code "165") (name "unconnected-(PCB1-136{slash}CAM0_DP0*-Pad136)") (class "Default")
      (node (ref "PCB1") (pin "136") (pinfunction "136/CAM0_DP0*_136") (pintype "bidirectional"))
    )
    (net (code "166") (name "unconnected-(PCB1-137{slash}CAM1_DN3*-Pad137)") (class "Default")
      (node (ref "PCB1") (pin "137") (pinfunction "137/CAM1_DN3*_137") (pintype "bidirectional"))
    )
    (net (code "167") (name "unconnected-(PCB1-138{slash}CAM0_DN0*-Pad138)") (class "Default")
      (node (ref "PCB1") (pin "138") (pinfunction "138/CAM0_DN0*_138") (pintype "bidirectional"))
    )
    (net (code "168") (name "unconnected-(PCB1-139{slash}GND-Pad139)") (class "Default")
      (node (ref "PCB1") (pin "139") (pinfunction "139/GND_139") (pintype "bidirectional"))
    )
    (net (code "169") (name "unconnected-(PCB1-140{slash}GND-Pad140)") (class "Default")
      (node (ref "PCB1") (pin "140") (pinfunction "140/GND_140") (pintype "bidirectional"))
    )
    (net (code "170") (name "unconnected-(PCB1-141{slash}CAM1_DP2*-Pad141)") (class "Default")
      (node (ref "PCB1") (pin "141") (pinfunction "141/CAM1_DP2*_141") (pintype "bidirectional"))
    )
    (net (code "171") (name "unconnected-(PCB1-142{slash}CAM0_CP*-Pad142)") (class "Default")
      (node (ref "PCB1") (pin "142") (pinfunction "142/CAM0_CP*_142") (pintype "bidirectional"))
    )
    (net (code "172") (name "unconnected-(PCB1-143{slash}CAM1_DN2*-Pad143)") (class "Default")
      (node (ref "PCB1") (pin "143") (pinfunction "143/CAM1_DN2*_143") (pintype "bidirectional"))
    )
    (net (code "173") (name "unconnected-(PCB1-144{slash}CAM0_CN*-Pad144)") (class "Default")
      (node (ref "PCB1") (pin "144") (pinfunction "144/CAM0_CN*_144") (pintype "bidirectional"))
    )
    (net (code "174") (name "unconnected-(PCB1-145{slash}GND-Pad145)") (class "Default")
      (node (ref "PCB1") (pin "145") (pinfunction "145/GND_145") (pintype "bidirectional"))
    )
    (net (code "175") (name "unconnected-(PCB1-146{slash}GND-Pad146)") (class "Default")
      (node (ref "PCB1") (pin "146") (pinfunction "146/GND_146") (pintype "bidirectional"))
    )
    (net (code "176") (name "unconnected-(PCB1-147{slash}CAM1_CP*-Pad147)") (class "Default")
      (node (ref "PCB1") (pin "147") (pinfunction "147/CAM1_CP*_147") (pintype "bidirectional"))
    )
    (net (code "177") (name "unconnected-(PCB1-148{slash}CAM0_DP1*-Pad148)") (class "Default")
      (node (ref "PCB1") (pin "148") (pinfunction "148/CAM0_DP1*_148") (pintype "bidirectional"))
    )
    (net (code "178") (name "unconnected-(PCB1-149{slash}CAM1_CN*-Pad149)") (class "Default")
      (node (ref "PCB1") (pin "149") (pinfunction "149/CAM1_CN*_149") (pintype "bidirectional"))
    )
    (net (code "179") (name "unconnected-(PCB1-150{slash}CAM0_DN1*-Pad150)") (class "Default")
      (node (ref "PCB1") (pin "150") (pinfunction "150/CAM0_DN1*_150") (pintype "bidirectional"))
    )
    (net (code "180") (name "unconnected-(PCB1-151{slash}GND-Pad151)") (class "Default")
      (node (ref "PCB1") (pin "151") (pinfunction "151/GND_151") (pintype "bidirectional"))
    )
    (net (code "181") (name "unconnected-(PCB1-152{slash}GND-Pad152)") (class "Default")
      (node (ref "PCB1") (pin "152") (pinfunction "152/GND_152") (pintype "bidirectional"))
    )
    (net (code "182") (name "unconnected-(PCB1-153{slash}CAM1_DP1*-Pad153)") (class "Default")
      (node (ref "PCB1") (pin "153") (pinfunction "153/CAM1_DP1*_153") (pintype "bidirectional"))
    )
    (net (code "183") (name "unconnected-(PCB1-154{slash}NC-Pad154)") (class "Default")
      (node (ref "PCB1") (pin "154") (pinfunction "154/NC_154") (pintype "bidirectional"))
    )
    (net (code "184") (name "unconnected-(PCB1-155{slash}CAM1_DN1*-Pad155)") (class "Default")
      (node (ref "PCB1") (pin "155") (pinfunction "155/CAM1_DN1*_155") (pintype "bidirectional"))
    )
    (net (code "185") (name "unconnected-(PCB1-156{slash}NC-Pad156)") (class "Default")
      (node (ref "PCB1") (pin "156") (pinfunction "156/NC_156") (pintype "bidirectional"))
    )
    (net (code "186") (name "unconnected-(PCB1-157{slash}GND-Pad157)") (class "Default")
      (node (ref "PCB1") (pin "157") (pinfunction "157/GND_157") (pintype "bidirectional"))
    )
    (net (code "187") (name "unconnected-(PCB1-158{slash}NC-Pad158)") (class "Default")
      (node (ref "PCB1") (pin "158") (pinfunction "158/NC_158") (pintype "bidirectional"))
    )
    (net (code "188") (name "unconnected-(PCB1-159{slash}CAM1_DP0*-Pad159)") (class "Default")
      (node (ref "PCB1") (pin "159") (pinfunction "159/CAM1_DP0*_159") (pintype "bidirectional"))
    )
    (net (code "189") (name "unconnected-(PCB1-160{slash}NC-Pad160)") (class "Default")
      (node (ref "PCB1") (pin "160") (pinfunction "160/NC_160") (pintype "bidirectional"))
    )
    (net (code "190") (name "unconnected-(PCB1-161{slash}CAM1_DN0*-Pad161)") (class "Default")
      (node (ref "PCB1") (pin "161") (pinfunction "161/CAM1_DN0*_161") (pintype "bidirectional"))
    )
    (net (code "191") (name "unconnected-(PCB1-162{slash}NC-Pad162)") (class "Default")
      (node (ref "PCB1") (pin "162") (pinfunction "162/NC_162") (pintype "bidirectional"))
    )
    (net (code "192") (name "unconnected-(PCB1-163{slash}GND-Pad163)") (class "Default")
      (node (ref "PCB1") (pin "163") (pinfunction "163/GND_163") (pintype "bidirectional"))
    )
    (net (code "193") (name "unconnected-(PCB1-164{slash}GND-Pad164)") (class "Default")
      (node (ref "PCB1") (pin "164") (pinfunction "164/GND_164") (pintype "bidirectional"))
    )
    (net (code "194") (name "unconnected-(PCB1-166{slash}TVDAC-Pad166)") (class "Default")
      (node (ref "PCB1") (pin "166") (pinfunction "166/TVDAC_166") (pintype "bidirectional"))
    )
    (net (code "195") (name "unconnected-(PCB1-168{slash}USB_OTGID-Pad168)") (class "Default")
      (node (ref "PCB1") (pin "168") (pinfunction "168/USB_OTGID_168") (pintype "bidirectional"))
    )
    (net (code "196") (name "unconnected-(PCB1-169{slash}GND-Pad169)") (class "Default")
      (node (ref "PCB1") (pin "169") (pinfunction "169/GND_169") (pintype "bidirectional"))
    )
    (net (code "197") (name "unconnected-(PCB1-170{slash}GND-Pad170)") (class "Default")
      (node (ref "PCB1") (pin "170") (pinfunction "170/GND_170") (pintype "bidirectional"))
    )
    (net (code "198") (name "unconnected-(PCB1-171{slash}HDMI_CEC-Pad171)") (class "Default")
      (node (ref "PCB1") (pin "171") (pinfunction "171/HDMI_CEC_171") (pintype "bidirectional"))
    )
    (net (code "199") (name "unconnected-(PCB1-172{slash}VC_TRST_N-Pad172)") (class "Default")
      (node (ref "PCB1") (pin "172") (pinfunction "172/VC_TRST_N_172") (pintype "bidirectional"))
    )
    (net (code "200") (name "unconnected-(PCB1-173{slash}HDMI_SDA-Pad173)") (class "Default")
      (node (ref "PCB1") (pin "173") (pinfunction "173/HDMI_SDA_173") (pintype "bidirectional"))
    )
    (net (code "201") (name "unconnected-(PCB1-174{slash}VC_TDI-Pad174)") (class "Default")
      (node (ref "PCB1") (pin "174") (pinfunction "174/VC_TDI_174") (pintype "bidirectional"))
    )
    (net (code "202") (name "unconnected-(PCB1-175{slash}HDMI_SCL-Pad175)") (class "Default")
      (node (ref "PCB1") (pin "175") (pinfunction "175/HDMI_SCL_175") (pintype "bidirectional"))
    )
    (net (code "203") (name "unconnected-(PCB1-176{slash}VC_TMS-Pad176)") (class "Default")
      (node (ref "PCB1") (pin "176") (pinfunction "176/VC_TMS_176") (pintype "bidirectional"))
    )
    (net (code "204") (name "unconnected-(PCB1-177{slash}RUN-Pad177)") (class "Default")
      (node (ref "PCB1") (pin "177") (pinfunction "177/RUN_177") (pintype "bidirectional"))
    )
    (net (code "205") (name "unconnected-(PCB1-178{slash}VC_TDO-Pad178)") (class "Default")
      (node (ref "PCB1") (pin "178") (pinfunction "178/VC_TDO_178") (pintype "bidirectional"))
    )
    (net (code "206") (name "unconnected-(PCB1-179{slash}VDD_CORE-Pad179)") (class "Default")
      (node (ref "PCB1") (pin "179") (pinfunction "179/VDD_CORE_179") (pintype "bidirectional"))
    )
    (net (code "207") (name "unconnected-(PCB1-180{slash}VC_TCK-Pad180)") (class "Default")
      (node (ref "PCB1") (pin "180") (pinfunction "180/VC_TCK_180") (pintype "bidirectional"))
    )
    (net (code "208") (name "unconnected-(PCB1-181{slash}GND-Pad181)") (class "Default")
      (node (ref "PCB1") (pin "181") (pinfunction "181/GND_181") (pintype "bidirectional"))
    )
    (net (code "209") (name "unconnected-(PCB1-182{slash}GND-Pad182)") (class "Default")
      (node (ref "PCB1") (pin "182") (pinfunction "182/GND_182") (pintype "bidirectional"))
    )
    (net (code "210") (name "unconnected-(PCB1-183{slash}1V8-Pad183)") (class "Default")
      (node (ref "PCB1") (pin "183") (pinfunction "183/1V8_183") (pintype "bidirectional"))
    )
    (net (code "211") (name "unconnected-(PCB1-184{slash}1V8-Pad184)") (class "Default")
      (node (ref "PCB1") (pin "184") (pinfunction "184/1V8_184") (pintype "bidirectional"))
    )
    (net (code "212") (name "unconnected-(PCB1-185{slash}1V8-Pad185)") (class "Default")
      (node (ref "PCB1") (pin "185") (pinfunction "185/1V8_185") (pintype "bidirectional"))
    )
    (net (code "213") (name "unconnected-(PCB1-186{slash}1V8-Pad186)") (class "Default")
      (node (ref "PCB1") (pin "186") (pinfunction "186/1V8_186") (pintype "bidirectional"))
    )
    (net (code "214") (name "unconnected-(PCB1-187{slash}GND-Pad187)") (class "Default")
      (node (ref "PCB1") (pin "187") (pinfunction "187/GND_187") (pintype "bidirectional"))
    )
    (net (code "215") (name "unconnected-(PCB1-188{slash}GND-Pad188)") (class "Default")
      (node (ref "PCB1") (pin "188") (pinfunction "188/GND_188") (pintype "bidirectional"))
    )
    (net (code "216") (name "unconnected-(PCB1-189{slash}VDAC-Pad189)") (class "Default")
      (node (ref "PCB1") (pin "189") (pinfunction "189/VDAC_189") (pintype "bidirectional"))
    )
    (net (code "217") (name "unconnected-(PCB1-190{slash}VDAC-Pad190)") (class "Default")
      (node (ref "PCB1") (pin "190") (pinfunction "190/VDAC_190") (pintype "bidirectional"))
    )
    (net (code "218") (name "unconnected-(PCB1-191{slash}3V3-Pad191)") (class "Default")
      (node (ref "PCB1") (pin "191") (pinfunction "191/3V3_191") (pintype "bidirectional"))
    )
    (net (code "219") (name "unconnected-(PCB1-192{slash}3V3-Pad192)") (class "Default")
      (node (ref "PCB1") (pin "192") (pinfunction "192/3V3_192") (pintype "bidirectional"))
    )
    (net (code "220") (name "unconnected-(PCB1-193{slash}3V3-Pad193)") (class "Default")
      (node (ref "PCB1") (pin "193") (pinfunction "193/3V3_193") (pintype "bidirectional"))
    )
    (net (code "221") (name "unconnected-(PCB1-194{slash}3V3-Pad194)") (class "Default")
      (node (ref "PCB1") (pin "194") (pinfunction "194/3V3_194") (pintype "bidirectional"))
    )
    (net (code "222") (name "unconnected-(PCB1-195{slash}GND-Pad195)") (class "Default")
      (node (ref "PCB1") (pin "195") (pinfunction "195/GND_195") (pintype "bidirectional"))
    )
    (net (code "223") (name "unconnected-(PCB1-196{slash}GND-Pad196)") (class "Default")
      (node (ref "PCB1") (pin "196") (pinfunction "196/GND_196") (pintype "bidirectional"))
    )
    (net (code "224") (name "unconnected-(PCB1-197{slash}VBAT-Pad197)") (class "Default")
      (node (ref "PCB1") (pin "197") (pinfunction "197/VBAT_197") (pintype "bidirectional"))
    )
    (net (code "225") (name "unconnected-(PCB1-198{slash}VBAT-Pad198)") (class "Default")
      (node (ref "PCB1") (pin "198") (pinfunction "198/VBAT_198") (pintype "bidirectional"))
    )
    (net (code "226") (name "unconnected-(PCB1-199{slash}VBAT-Pad199)") (class "Default")
      (node (ref "PCB1") (pin "199") (pinfunction "199/VBAT_199") (pintype "bidirectional"))
    )
    (net (code "227") (name "unconnected-(PCB1-200{slash}VBAT-Pad200)") (class "Default")
      (node (ref "PCB1") (pin "200") (pinfunction "200/VBAT_200") (pintype "bidirectional"))
    )
    (net (code "228") (name "unconnected-(U$1-PadL)") (class "Default")
      (node (ref "U$1") (pin "L") (pinfunction "L_L") (pintype "bidirectional"))
    )
    (net (code "229") (name "unconnected-(U$1-PadN)") (class "Default")
      (node (ref "U$1") (pin "N") (pinfunction "N_N") (pintype "bidirectional"))
    )
    (net (code "230") (name "unconnected-(U$1-PadPE)") (class "Default")
      (node (ref "U$1") (pin "PE") (pinfunction "PE_PE") (pintype "bidirectional"))
    )
    (net (code "231") (name "unconnected-(U$2-AC-L-PadAC{slash}L)") (class "Default")
      (node (ref "U$2") (pin "AC/L") (pinfunction "AC-L_AC/L") (pintype "bidirectional"))
    )
    (net (code "232") (name "unconnected-(U$2-AC-N-PadAC{slash}N)") (class "Default")
      (node (ref "U$2") (pin "AC/N") (pinfunction "AC-N_AC/N") (pintype "bidirectional"))
    )
    (net (code "233") (name "unconnected-(U$2-V+-Pad+V)") (class "Default")
      (node (ref "U$2") (pin "+V") (pinfunction "V+_+V") (pintype "bidirectional"))
    )
    (net (code "234") (name "unconnected-(U$2-V--Pad-V)") (class "Default")
      (node (ref "U$2") (pin "-V") (pinfunction "V-_-V") (pintype "bidirectional"))
    )
    (net (code "235") (name "unconnected-(U1-EECLK-Pad26)") (class "Default")
      (node (ref "U1") (pin "26") (pinfunction "EECLK_26") (pintype "input"))
    )
    (net (code "236") (name "unconnected-(U1-EECS-Pad29)") (class "Default")
      (node (ref "U1") (pin "29") (pinfunction "EECS_29") (pintype "input"))
    )
    (net (code "237") (name "unconnected-(U1-EEDI-Pad27)") (class "Default")
      (node (ref "U1") (pin "27") (pinfunction "EEDI_27") (pintype "input"))
    )
    (net (code "238") (name "unconnected-(U1-EEDO-Pad28)") (class "Default")
      (node (ref "U1") (pin "28") (pinfunction "EEDO_28") (pintype "output"))
    )
    (net (code "239") (name "unconnected-(U1-GPIO0{slash}LED0-Pad31)") (class "Default")
      (node (ref "U1") (pin "31") (pinfunction "GPIO0/LED0_31") (pintype "bidirectional"))
    )
    (net (code "240") (name "unconnected-(U1-GPIO1{slash}LED1-Pad32)") (class "Default")
      (node (ref "U1") (pin "32") (pinfunction "GPIO1/LED1_32") (pintype "bidirectional"))
    )
    (net (code "241") (name "unconnected-(U1-GPIO2{slash}LED2-Pad33)") (class "Default")
      (node (ref "U1") (pin "33") (pinfunction "GPIO2/LED2_33") (pintype "bidirectional"))
    )
    (net (code "242") (name "unconnected-(U1-GPIO3{slash}LED3-Pad34)") (class "Default")
      (node (ref "U1") (pin "34") (pinfunction "GPIO3/LED3_34") (pintype "bidirectional"))
    )
    (net (code "243") (name "unconnected-(U1-GPIO4{slash}LED4-Pad35)") (class "Default")
      (node (ref "U1") (pin "35") (pinfunction "GPIO4/LED4_35") (pintype "bidirectional"))
    )
    (net (code "244") (name "unconnected-(U1-GPIO5{slash}PME-Pad38)") (class "Default")
      (node (ref "U1") (pin "38") (pinfunction "GPIO5/PME_38") (pintype "bidirectional"))
    )
    (net (code "245") (name "unconnected-(U1-GPIO6{slash}PME_MODE_SEL-Pad40)") (class "Default")
      (node (ref "U1") (pin "40") (pinfunction "GPIO6/PME_MODE_SEL_40") (pintype "bidirectional"))
    )
    (net (code "246") (name "unconnected-(U1-GPIO7-Pad10)") (class "Default")
      (node (ref "U1") (pin "10") (pinfunction "GPIO7_10") (pintype "bidirectional"))
    )
    (net (code "247") (name "unconnected-(U1-GPIO8-Pad18)") (class "Default")
      (node (ref "U1") (pin "18") (pinfunction "GPIO8_18") (pintype "bidirectional"))
    )
    (net (code "248") (name "unconnected-(U1-GPIO9-Pad21)") (class "Default")
      (node (ref "U1") (pin "21") (pinfunction "GPIO9_21") (pintype "bidirectional"))
    )
    (net (code "249") (name "unconnected-(U1-GPIO10-Pad22)") (class "Default")
      (node (ref "U1") (pin "22") (pinfunction "GPIO10_22") (pintype "bidirectional"))
    )
    (net (code "250") (name "unconnected-(U1-GPIO11-Pad25)") (class "Default")
      (node (ref "U1") (pin "25") (pinfunction "GPIO11_25") (pintype "bidirectional"))
    )
    (net (code "251") (name "unconnected-(U1-SW_MODE-Pad9)") (class "Default")
      (node (ref "U1") (pin "9") (pinfunction "SW_MODE_9") (pintype "output"))
    )
    (net (code "252") (name "unconnected-(U1-TCK-Pad2)") (class "Default")
      (node (ref "U1") (pin "2") (pinfunction "TCK_2") (pintype "input"))
    )
    (net (code "253") (name "unconnected-(U1-TDI-Pad1)") (class "Default")
      (node (ref "U1") (pin "1") (pinfunction "TDI_1") (pintype "input"))
    )
    (net (code "254") (name "unconnected-(U1-TDO-Pad4)") (class "Default")
      (node (ref "U1") (pin "4") (pinfunction "TDO_4") (pintype "output"))
    )
    (net (code "255") (name "unconnected-(U1-TEST-Pad39)") (class "Default")
      (node (ref "U1") (pin "39") (pinfunction "TEST_39") (pintype "input"))
    )
    (net (code "256") (name "unconnected-(U1-TMS-Pad3)") (class "Default")
      (node (ref "U1") (pin "3") (pinfunction "TMS_3") (pintype "input"))
    )
    (net (code "257") (name "unconnected-(U1-XI-Pad5)") (class "Default")
      (node (ref "U1") (pin "5") (pinfunction "XI_5") (pintype "input"))
    )
    (net (code "258") (name "unconnected-(U1-XO-Pad6)") (class "Default")
      (node (ref "U1") (pin "6") (pinfunction "XO_6") (pintype "output"))
    )
    (net (code "259") (name "unconnected-(U1-~{RESET}{slash}PME_CLEAR-Pad42)") (class "Default")
      (node (ref "U1") (pin "42") (pinfunction "~{RESET}/PME_CLEAR_42") (pintype "input"))
    )
  )
)
